# mixer.net
KiCad netlist of a schematic drawn in EAGLE
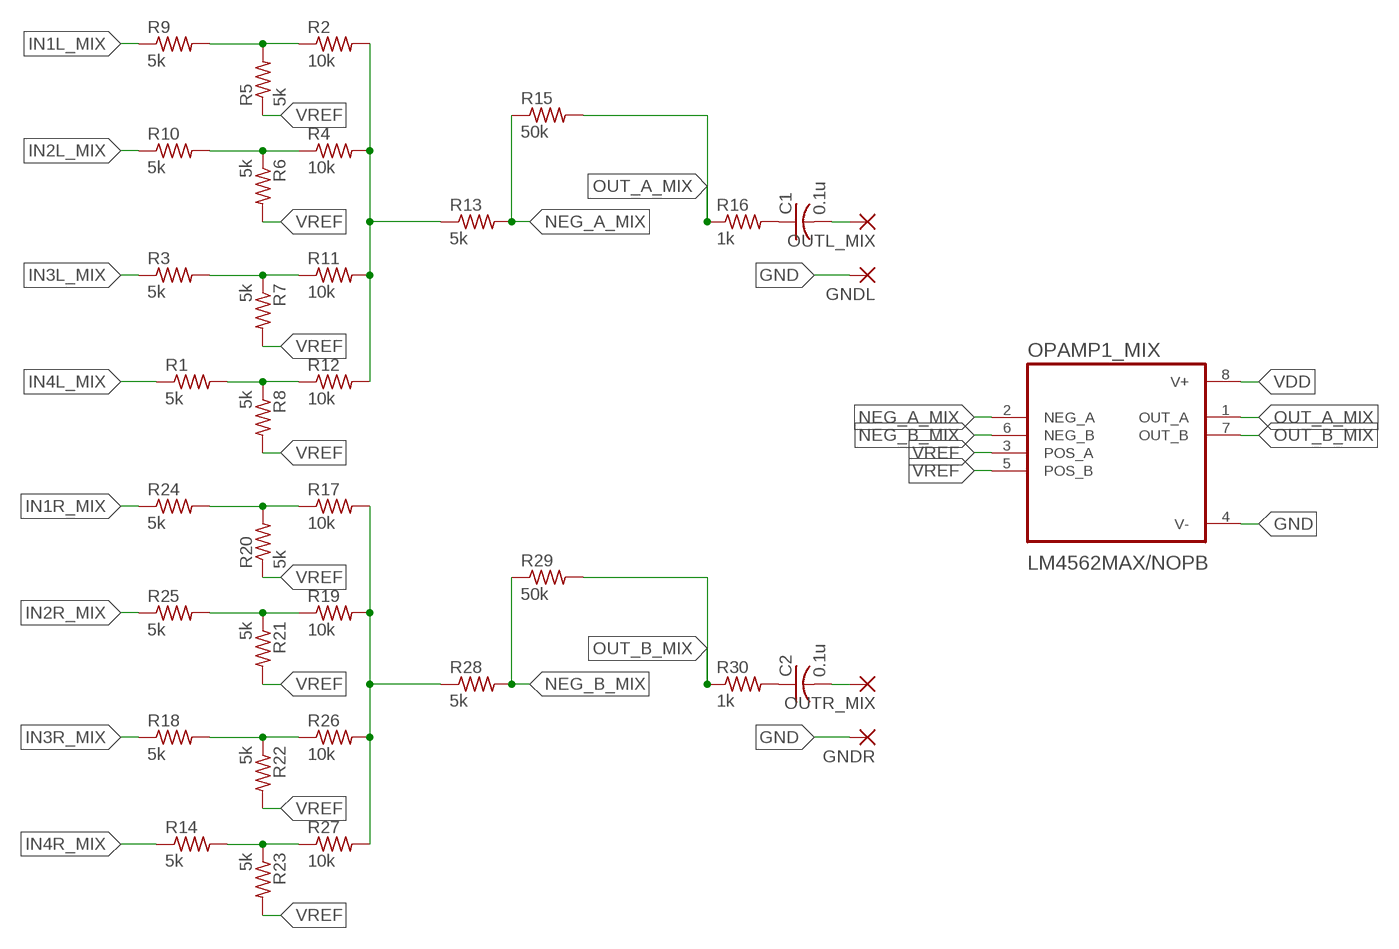
[diagram p0: schematic, sheet 1]

(export (version "E")
  (design (tool "Eeschema 10.0.6"))
  (components
    (comp (ref "C1")
      (value "0.1u")
      (footprint "eagle-import:C0402")
      (libsource (lib "eagle-import") (part "C-USC0402"))
    )
    (comp (ref "C2")
      (value "0.1u")
      (footprint "eagle-import:C0402")
      (libsource (lib "eagle-import") (part "C-USC0402"))
    )
    (comp (ref "GNDL")
      (value "SMD5")
      (footprint "eagle-import:SMD2,54-5,08")
      (libsource (lib "eagle-import") (part "SMD5"))
    )
    (comp (ref "GNDR")
      (value "SMD5")
      (footprint "eagle-import:SMD2,54-5,08")
      (libsource (lib "eagle-import") (part "SMD5"))
    )
    (comp (ref "OPAMP1_MIX")
      (value "LM4562MAX/NOPB")
      (footprint "eagle-import:SOIC127P599X175-8N")
      (fields (field (name "MF") "Texas Instruments"))
      (libsource (lib "eagle-import") (part "LM4562MAX/NOPB"))
    )
    (comp (ref "OUTL_MIX")
      (value "SMD5")
      (footprint "eagle-import:SMD2,54-5,08")
      (libsource (lib "eagle-import") (part "SMD5"))
    )
    (comp (ref "OUTR_MIX")
      (value "SMD5")
      (footprint "eagle-import:SMD2,54-5,08")
      (libsource (lib "eagle-import") (part "SMD5"))
    )
    (comp (ref "R1")
      (value "5k")
      (footprint "eagle-import:R0402")
      (libsource (lib "eagle-import") (part "R-US_R0402"))
    )
    (comp (ref "R2")
      (value "10k")
      (footprint "eagle-import:R0402")
      (libsource (lib "eagle-import") (part "R-US_R0402"))
    )
    (comp (ref "R3")
      (value "5k")
      (footprint "eagle-import:R0402")
      (libsource (lib "eagle-import") (part "R-US_R0402"))
    )
    (comp (ref "R4")
      (value "10k")
      (footprint "eagle-import:R0402")
      (libsource (lib "eagle-import") (part "R-US_R0402"))
    )
    (comp (ref "R5")
      (value "5k")
      (footprint "eagle-import:R0402")
      (libsource (lib "eagle-import") (part "R-US_R0402"))
    )
    (comp (ref "R6")
      (value "5k")
      (footprint "eagle-import:R0402")
      (libsource (lib "eagle-import") (part "R-US_R0402"))
    )
    (comp (ref "R7")
      (value "5k")
      (footprint "eagle-import:R0402")
      (libsource (lib "eagle-import") (part "R-US_R0402"))
    )
    (comp (ref "R8")
      (value "5k")
      (footprint "eagle-import:R0402")
      (libsource (lib "eagle-import") (part "R-US_R0402"))
    )
    (comp (ref "R9")
      (value "5k")
      (footprint "eagle-import:R0402")
      (libsource (lib "eagle-import") (part "R-US_R0402"))
    )
    (comp (ref "R10")
      (value "5k")
      (footprint "eagle-import:R0402")
      (libsource (lib "eagle-import") (part "R-US_R0402"))
    )
    (comp (ref "R11")
      (value "10k")
      (footprint "eagle-import:R0402")
      (libsource (lib "eagle-import") (part "R-US_R0402"))
    )
    (comp (ref "R12")
      (value "10k")
      (footprint "eagle-import:R0402")
      (libsource (lib "eagle-import") (part "R-US_R0402"))
    )
    (comp (ref "R13")
      (value "5k")
      (footprint "eagle-import:R0402")
      (libsource (lib "eagle-import") (part "R-US_R0402"))
    )
    (comp (ref "R14")
      (value "5k")
      (footprint "eagle-import:R0402")
      (libsource (lib "eagle-import") (part "R-US_R0402"))
    )
    (comp (ref "R15")
      (value "50k")
      (footprint "eagle-import:R0402")
      (libsource (lib "eagle-import") (part "R-US_R0402"))
    )
    (comp (ref "R16")
      (value "1k")
      (footprint "eagle-import:R0402")
      (libsource (lib "eagle-import") (part "R-US_R0402"))
    )
    (comp (ref "R17")
      (value "10k")
      (footprint "eagle-import:R0402")
      (libsource (lib "eagle-import") (part "R-US_R0402"))
    )
    (comp (ref "R18")
      (value "5k")
      (footprint "eagle-import:R0402")
      (libsource (lib "eagle-import") (part "R-US_R0402"))
    )
    (comp (ref "R19")
      (value "10k")
      (footprint "eagle-import:R0402")
      (libsource (lib "eagle-import") (part "R-US_R0402"))
    )
    (comp (ref "R20")
      (value "5k")
      (footprint "eagle-import:R0402")
      (libsource (lib "eagle-import") (part "R-US_R0402"))
    )
    (comp (ref "R21")
      (value "5k")
      (footprint "eagle-import:R0402")
      (libsource (lib "eagle-import") (part "R-US_R0402"))
    )
    (comp (ref "R22")
      (value "5k")
      (footprint "eagle-import:R0402")
      (libsource (lib "eagle-import") (part "R-US_R0402"))
    )
    (comp (ref "R23")
      (value "5k")
      (footprint "eagle-import:R0402")
      (libsource (lib "eagle-import") (part "R-US_R0402"))
    )
    (comp (ref "R24")
      (value "5k")
      (footprint "eagle-import:R0402")
      (libsource (lib "eagle-import") (part "R-US_R0402"))
    )
    (comp (ref "R25")
      (value "5k")
      (footprint "eagle-import:R0402")
      (libsource (lib "eagle-import") (part "R-US_R0402"))
    )
    (comp (ref "R26")
      (value "10k")
      (footprint "eagle-import:R0402")
      (libsource (lib "eagle-import") (part "R-US_R0402"))
    )
    (comp (ref "R27")
      (value "10k")
      (footprint "eagle-import:R0402")
      (libsource (lib "eagle-import") (part "R-US_R0402"))
    )
    (comp (ref "R28")
      (value "5k")
      (footprint "eagle-import:R0402")
      (libsource (lib "eagle-import") (part "R-US_R0402"))
    )
    (comp (ref "R29")
      (value "50k")
      (footprint "eagle-import:R0402")
      (libsource (lib "eagle-import") (part "R-US_R0402"))
    )
    (comp (ref "R30")
      (value "1k")
      (footprint "eagle-import:R0402")
      (libsource (lib "eagle-import") (part "R-US_R0402"))
    )
  )
  (nets
    (net (code "1") (name "GND") (class "Default")
      (node (ref "GNDL") (pin "1") (pinfunction "P_1") (pintype "passive"))
      (node (ref "GNDR") (pin "1") (pinfunction "P_1") (pintype "passive"))
      (node (ref "OPAMP1_MIX") (pin "4") (pinfunction "V-_4") (pintype "power_in"))
    )
    (net (code "2") (name "IN1L_MIX") (class "Default")
      (node (ref "R9") (pin "1") (pinfunction "1_1") (pintype "passive"))
    )
    (net (code "3") (name "IN1R_MIX") (class "Default")
      (node (ref "R24") (pin "1") (pinfunction "1_1") (pintype "passive"))
    )
    (net (code "4") (name "IN2L_MIX") (class "Default")
      (node (ref "R10") (pin "1") (pinfunction "1_1") (pintype "passive"))
    )
    (net (code "5") (name "IN2R_MIX") (class "Default")
      (node (ref "R25") (pin "1") (pinfunction "1_1") (pintype "passive"))
    )
    (net (code "6") (name "IN3L_MIX") (class "Default")
      (node (ref "R3") (pin "1") (pinfunction "1_1") (pintype "passive"))
    )
    (net (code "7") (name "IN3R_MIX") (class "Default")
      (node (ref "R18") (pin "1") (pinfunction "1_1") (pintype "passive"))
    )
    (net (code "8") (name "IN4L_MIX") (class "Default")
      (node (ref "R1") (pin "1") (pinfunction "1_1") (pintype "passive"))
    )
    (net (code "9") (name "IN4R_MIX") (class "Default")
      (node (ref "R14") (pin "1") (pinfunction "1_1") (pintype "passive"))
    )
    (net (code "10") (name "NEG_A_MIX") (class "Default")
      (node (ref "OPAMP1_MIX") (pin "2") (pinfunction "NEG_A_2") (pintype "input"))
      (node (ref "R13") (pin "2") (pinfunction "2_2") (pintype "passive"))
      (node (ref "R15") (pin "1") (pinfunction "1_1") (pintype "passive"))
    )
    (net (code "11") (name "NEG_B_MIX") (class "Default")
      (node (ref "OPAMP1_MIX") (pin "6") (pinfunction "NEG_B_6") (pintype "input"))
      (node (ref "R28") (pin "2") (pinfunction "2_2") (pintype "passive"))
      (node (ref "R29") (pin "1") (pinfunction "1_1") (pintype "passive"))
    )
    (net (code "12") (name "Net-(C1-Pad1)") (class "Default")
      (node (ref "C1") (pin "1") (pinfunction "1_1") (pintype "passive"))
      (node (ref "R16") (pin "2") (pinfunction "2_2") (pintype "passive"))
    )
    (net (code "13") (name "Net-(C2-Pad1)") (class "Default")
      (node (ref "C2") (pin "1") (pinfunction "1_1") (pintype "passive"))
      (node (ref "R30") (pin "2") (pinfunction "2_2") (pintype "passive"))
    )
    (net (code "14") (name "Net-(OUTL_MIX-P)") (class "Default")
      (node (ref "C1") (pin "2") (pinfunction "2_2") (pintype "passive"))
      (node (ref "OUTL_MIX") (pin "1") (pinfunction "P_1") (pintype "passive"))
    )
    (net (code "15") (name "Net-(OUTR_MIX-P)") (class "Default")
      (node (ref "C2") (pin "2") (pinfunction "2_2") (pintype "passive"))
      (node (ref "OUTR_MIX") (pin "1") (pinfunction "P_1") (pintype "passive"))
    )
    (net (code "16") (name "Net-(R1-Pad2)") (class "Default")
      (node (ref "R1") (pin "2") (pinfunction "2_2") (pintype "passive"))
      (node (ref "R12") (pin "1") (pinfunction "1_1") (pintype "passive"))
      (node (ref "R8") (pin "1") (pinfunction "1_1") (pintype "passive"))
    )
    (net (code "17") (name "Net-(R2-Pad1)") (class "Default")
      (node (ref "R2") (pin "1") (pinfunction "1_1") (pintype "passive"))
      (node (ref "R5") (pin "2") (pinfunction "2_2") (pintype "passive"))
      (node (ref "R9") (pin "2") (pinfunction "2_2") (pintype "passive"))
    )
    (net (code "18") (name "Net-(R10-Pad2)") (class "Default")
      (node (ref "R10") (pin "2") (pinfunction "2_2") (pintype "passive"))
      (node (ref "R4") (pin "1") (pinfunction "1_1") (pintype "passive"))
      (node (ref "R6") (pin "1") (pinfunction "1_1") (pintype "passive"))
    )
    (net (code "19") (name "Net-(R11-Pad1)") (class "Default")
      (node (ref "R11") (pin "1") (pinfunction "1_1") (pintype "passive"))
      (node (ref "R3") (pin "2") (pinfunction "2_2") (pintype "passive"))
      (node (ref "R7") (pin "1") (pinfunction "1_1") (pintype "passive"))
    )
    (net (code "20") (name "Net-(R11-Pad2)") (class "Default")
      (node (ref "R11") (pin "2") (pinfunction "2_2") (pintype "passive"))
      (node (ref "R12") (pin "2") (pinfunction "2_2") (pintype "passive"))
      (node (ref "R13") (pin "1") (pinfunction "1_1") (pintype "passive"))
      (node (ref "R2") (pin "2") (pinfunction "2_2") (pintype "passive"))
      (node (ref "R4") (pin "2") (pinfunction "2_2") (pintype "passive"))
    )
    (net (code "21") (name "Net-(R14-Pad2)") (class "Default")
      (node (ref "R14") (pin "2") (pinfunction "2_2") (pintype "passive"))
      (node (ref "R23") (pin "1") (pinfunction "1_1") (pintype "passive"))
      (node (ref "R27") (pin "1") (pinfunction "1_1") (pintype "passive"))
    )
    (net (code "22") (name "Net-(R17-Pad1)") (class "Default")
      (node (ref "R17") (pin "1") (pinfunction "1_1") (pintype "passive"))
      (node (ref "R20") (pin "2") (pinfunction "2_2") (pintype "passive"))
      (node (ref "R24") (pin "2") (pinfunction "2_2") (pintype "passive"))
    )
    (net (code "23") (name "Net-(R17-Pad2)") (class "Default")
      (node (ref "R17") (pin "2") (pinfunction "2_2") (pintype "passive"))
      (node (ref "R19") (pin "2") (pinfunction "2_2") (pintype "passive"))
      (node (ref "R26") (pin "2") (pinfunction "2_2") (pintype "passive"))
      (node (ref "R27") (pin "2") (pinfunction "2_2") (pintype "passive"))
      (node (ref "R28") (pin "1") (pinfunction "1_1") (pintype "passive"))
    )
    (net (code "24") (name "Net-(R18-Pad2)") (class "Default")
      (node (ref "R18") (pin "2") (pinfunction "2_2") (pintype "passive"))
      (node (ref "R22") (pin "1") (pinfunction "1_1") (pintype "passive"))
      (node (ref "R26") (pin "1") (pinfunction "1_1") (pintype "passive"))
    )
    (net (code "25") (name "Net-(R19-Pad1)") (class "Default")
      (node (ref "R19") (pin "1") (pinfunction "1_1") (pintype "passive"))
      (node (ref "R21") (pin "1") (pinfunction "1_1") (pintype "passive"))
      (node (ref "R25") (pin "2") (pinfunction "2_2") (pintype "passive"))
    )
    (net (code "26") (name "OUT_A_MIX") (class "Default")
      (node (ref "OPAMP1_MIX") (pin "1") (pinfunction "OUT_A_1") (pintype "output"))
      (node (ref "R15") (pin "2") (pinfunction "2_2") (pintype "passive"))
      (node (ref "R16") (pin "1") (pinfunction "1_1") (pintype "passive"))
    )
    (net (code "27") (name "OUT_B_MIX") (class "Default")
      (node (ref "OPAMP1_MIX") (pin "7") (pinfunction "OUT_B_7") (pintype "output"))
      (node (ref "R29") (pin "2") (pinfunction "2_2") (pintype "passive"))
      (node (ref "R30") (pin "1") (pinfunction "1_1") (pintype "passive"))
    )
    (net (code "28") (name "VDD") (class "Default")
      (node (ref "OPAMP1_MIX") (pin "8") (pinfunction "V+_8") (pintype "power_in"))
    )
    (net (code "29") (name "VREF") (class "Default")
      (node (ref "OPAMP1_MIX") (pin "3") (pinfunction "POS_A_3") (pintype "input"))
      (node (ref "OPAMP1_MIX") (pin "5") (pinfunction "POS_B_5") (pintype "input"))
      (node (ref "R20") (pin "1") (pinfunction "1_1") (pintype "passive"))
      (node (ref "R21") (pin "2") (pinfunction "2_2") (pintype "passive"))
      (node (ref "R22") (pin "2") (pinfunction "2_2") (pintype "passive"))
      (node (ref "R23") (pin "2") (pinfunction "2_2") (pintype "passive"))
      (node (ref "R5") (pin "1") (pinfunction "1_1") (pintype "passive"))
      (node (ref "R6") (pin "2") (pinfunction "2_2") (pintype "passive"))
      (node (ref "R7") (pin "2") (pinfunction "2_2") (pintype "passive"))
      (node (ref "R8") (pin "2") (pinfunction "2_2") (pintype "passive"))
    )
  )
)
